# Probatio_Pogo.net
KiCad netlist of a schematic drawn in EAGLE
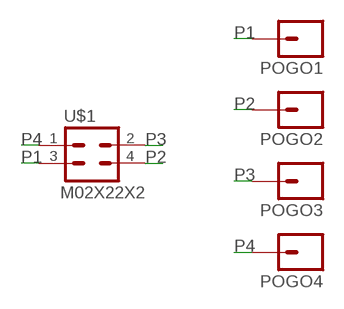
[diagram p0: schematic, sheet 1]

(export (version "E")
  (design (tool "Eeschema 10.0.6"))
  (components
    (comp (ref "POGO1")
      (value "POGO_PIN0900-0-15-20-76-14-11-0")
      (footprint "eagle-import:POGO_PIN")
      (libsource (lib "eagle-import") (part "POGO_PIN0900-0-15-20-76-14-11-0"))
    )
    (comp (ref "POGO2")
      (value "POGO_PIN0900-0-15-20-76-14-11-0")
      (footprint "eagle-import:POGO_PIN")
      (libsource (lib "eagle-import") (part "POGO_PIN0900-0-15-20-76-14-11-0"))
    )
    (comp (ref "POGO3")
      (value "POGO_PIN0900-0-15-20-76-14-11-0")
      (footprint "eagle-import:POGO_PIN")
      (libsource (lib "eagle-import") (part "POGO_PIN0900-0-15-20-76-14-11-0"))
    )
    (comp (ref "POGO4")
      (value "POGO_PIN0900-0-15-20-76-14-11-0")
      (footprint "eagle-import:POGO_PIN")
      (libsource (lib "eagle-import") (part "POGO_PIN0900-0-15-20-76-14-11-0"))
    )
    (comp (ref "U$1")
      (value "M02X22X2")
      (footprint "eagle-import:2X2")
      (libsource (lib "eagle-import") (part "M02X22X2"))
    )
  )
  (nets
    (net (code "1") (name "/P1") (class "Default")
      (node (ref "POGO1") (pin "P$1") (pinfunction "1_P$1") (pintype "passive"))
      (node (ref "U$1") (pin "3") (pinfunction "3_3") (pintype "passive"))
    )
    (net (code "2") (name "/P2") (class "Default")
      (node (ref "POGO2") (pin "P$1") (pinfunction "1_P$1") (pintype "passive"))
      (node (ref "U$1") (pin "4") (pinfunction "4_4") (pintype "passive"))
    )
    (net (code "3") (name "/P3") (class "Default")
      (node (ref "POGO3") (pin "P$1") (pinfunction "1_P$1") (pintype "passive"))
      (node (ref "U$1") (pin "2") (pinfunction "2_2") (pintype "passive"))
    )
    (net (code "4") (name "/P4") (class "Default")
      (node (ref "POGO4") (pin "P$1") (pinfunction "1_P$1") (pintype "passive"))
      (node (ref "U$1") (pin "1") (pinfunction "1_1") (pintype "passive"))
    )
  )
)
